# Synchronous_Rectification_and_Filtering.net
KiCad netlist of a schematic drawn in Altium Designer
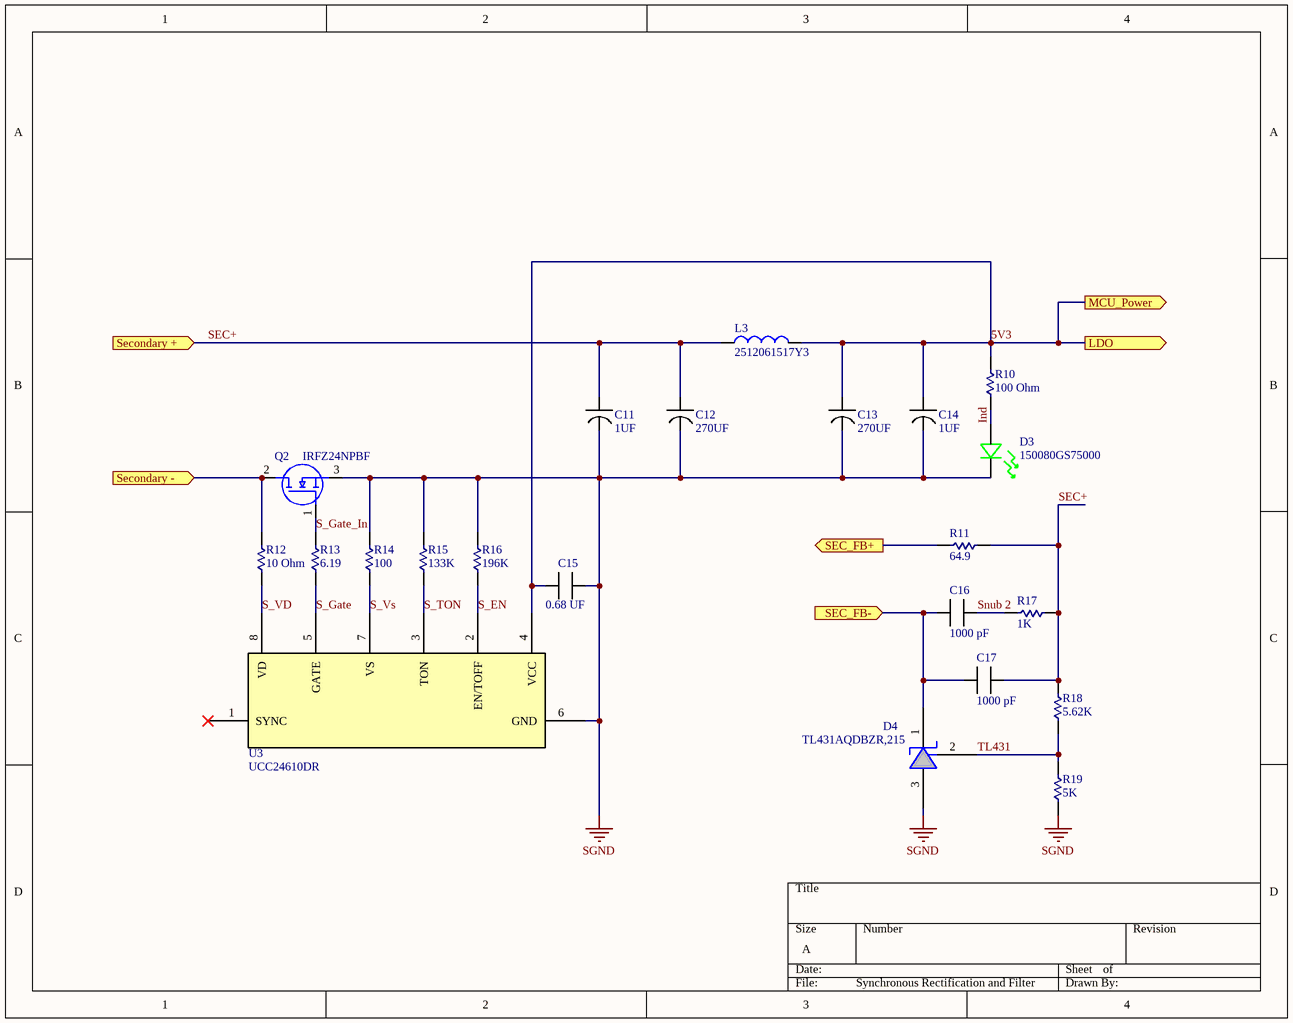
[diagram p0: Synchronous Rectification and Filtering.SchDoc]

(export (version "E")
  (design (tool "Eeschema 10.0.6"))
  (components
    (comp (ref "C11")
      (value "1UF")
      (footprint "CAP TANTALUM 1206")
      (description "Tantalum Capacitors - Solid SMD 10v 1uF 1206 10% ESR=10Ohms")
      (libsource (lib "SMPS Schlib") (part "T491A105K010AT"))
    )
    (comp (ref "C12")
      (value "270UF")
      (footprint "Alum Radial Cap 5mm")
      (description "Aluminum Electrolytic Capacitors - Radial Leaded 50V 270uF 105C 4k Hour Radial")
      (libsource (lib "SMPS Schlib") (part "ESY277M050AH4AA"))
    )
    (comp (ref "C13")
      (value "270UF")
      (footprint "Alum Radial Cap 5mm")
      (description "Aluminum Electrolytic Capacitors - Radial Leaded 50V 270uF 105C 4k Hour Radial")
      (libsource (lib "SMPS Schlib") (part "ESY277M050AH4AA"))
    )
    (comp (ref "C14")
      (value "1UF")
      (footprint "CAP TANTALUM 1206")
      (description "Tantalum Capacitors - Solid SMD 10v 1uF 1206 10% ESR=10Ohms")
      (libsource (lib "SMPS Schlib") (part "T491A105K010AT"))
    )
    (comp (ref "C15")
      (value "0.68 UF")
      (footprint "Res 0805")
      (description "Multilayer Ceramic Capacitors MLCC - SMD/SMT 50V 0.68uF X7R 0805 10% AEC-Q200")
      (libsource (lib "SMPS Schlib") (part "C0805C684K5RACAUTO7210"))
    )
    (comp (ref "C16")
      (value "1000 pF")
      (footprint "Cap 0603")
      (description "Multilayer Ceramic Capacitors MLCC - SMD/SMT 100V 1000pF X7R 0603 10%")
      (libsource (lib "SMPS Schlib") (part "C0603C102K1RAC7411"))
    )
    (comp (ref "C17")
      (value "1000 pF")
      (footprint "Cap 0603")
      (description "Multilayer Ceramic Capacitors MLCC - SMD/SMT 100V 1000pF X7R 0603 10%")
      (libsource (lib "SMPS Schlib") (part "C0603C102K1RAC7411"))
    )
    (comp (ref "D3")
      (value "150080GS75000")
      (footprint "Res 0805")
      (description "Standard LEDs - SMD WL-SMCW SMDMono TpVw Waterclr 0805 Green")
      (libsource (lib "SMPS Schlib") (part "150080GS75000"))
    )
    (comp (ref "D4")
      (value "TL431AQDBZR,215")
      (footprint "SOT23(TO-236AB)_NEX")
      (description "Shunt Voltage Reference IC Adjustable 2.495V 36 VV ±1% 100 mA TO-236AB")
      (libsource (lib "SMPS Schlib") (part "TL431AQDBZR,215"))
    )
    (comp (ref "L3")
      (value "2512061517Y3")
      (footprint "IND 1206")
      (description "Ferrite Beads MULTILAYER CHIP BEAD Z=150 OHM@100MHz 25")
      (libsource (lib "SMPS Schlib") (part "2512061517Y3"))
    )
    (comp (ref "Q2")
      (value "IRFZ24NPBF")
      (footprint "TO-220-3")
      (description "MOSFET MOSFT 55V 17A 70mOhm 13.3nC")
      (libsource (lib "SMPS Schlib") (part "IRFZ24NPBF"))
    )
    (comp (ref "R10")
      (value "100 Ohm")
      (footprint "Res 0805")
      (description "Thick Film Resistors - SMD 100 Ohms 125 mW 0805 1%")
      (libsource (lib "SMPS Schlib") (part "RC0805FR-07100RL"))
    )
    (comp (ref "R11")
      (value "64.9")
      (footprint "Res 0805")
      (description "Thin Film Resistors - SMD 1/8W 64.9 ohm 1% 50ppm")
      (libsource (lib "SMPS Schlib") (part "RT0805FRE0764R9L"))
    )
    (comp (ref "R12")
      (value "10 Ohm")
      (footprint "Res 0805")
      (description "Thick Film Resistors - SMD 10Ohms 1/8W 0805 5% 5% AEC-Q200")
      (libsource (lib "SMPS Schlib") (part "AR0805JR-0710RL"))
    )
    (comp (ref "R13")
      (value "6.19")
      (footprint "Res 0805")
      (description "Thick Film Resistors - SMD 6.19 Ohms 125 mW 0805 1%")
      (libsource (lib "SMPS Schlib") (part "RC0805FR-076R19L"))
    )
    (comp (ref "R14")
      (value "100")
      (footprint "Res 0805")
      (description "Thick Film Resistors - SMD 100 Ohms 125 mW 0805 1%")
      (libsource (lib "SMPS Schlib") (part "RC0805FR-07100RL"))
    )
    (comp (ref "R15")
      (value "133K")
      (footprint "Res 0805")
      (description "Thin Film Resistors - SMD 1/8W 133K ohm 1% 50ppm")
      (libsource (lib "SMPS Schlib") (part "RT0805FRE07133KL"))
    )
    (comp (ref "R16")
      (value "196K")
      (footprint "Res 0805")
      (description "Thin Film Resistors - SMD 1/8W 196K ohm 1% 50ppm")
      (libsource (lib "SMPS Schlib") (part "RT0805FRE07196KL"))
    )
    (comp (ref "R17")
      (value "1K")
      (footprint "Res 0805")
      (description "Thick Film Resistors - SMD 1 kOhms 250mW 0805 1 % AEC-Q200 Double Power Version")
      (libsource (lib "SMPS Schlib") (part "AC0805FR-7W1KL"))
    )
    (comp (ref "R18")
      (value "5.62K")
      (footprint "Res 0805")
      (description "Thin Film Resistors - SMD 1/8W 5.62K ohm .1% 25ppm")
      (libsource (lib "SMPS Schlib") (part "RT0805BRD075K62L"))
    )
    (comp (ref "R19")
      (value "5K")
      (footprint "Res 0805")
      (description "Thin Film Resistors - SMD 5K OHM .1% 25PPM 1/8W")
      (libsource (lib "SMPS Schlib") (part "CRT0805-BY-5001EAS"))
    )
    (comp (ref "U3")
      (value "UCC24610DR")
      (footprint "SOIC-8")
      (description "Gate Drivers Secondary Side Sync Rectifier Controller")
      (libsource (lib "SMPS Schlib") (part "UCC24610DR"))
    )
  )
  (nets
    (net (code "1") (name "/5V3") (class "Default")
      (node (ref "C13") (pin "1") (pinfunction "1_1") (pintype "passive"))
      (node (ref "C14") (pin "1") (pinfunction "1_1") (pintype "passive"))
      (node (ref "C15") (pin "2") (pinfunction "2_2") (pintype "passive"))
      (node (ref "L3") (pin "2") (pinfunction "2_2") (pintype "passive"))
      (node (ref "R10") (pin "2") (pinfunction "B_2") (pintype "passive"))
      (node (ref "U3") (pin "4") (pinfunction "VCC_4") (pintype "passive"))
    )
    (net (code "2") (name "/Ind") (class "Default")
      (node (ref "D3") (pin "2") (pinfunction "2_2") (pintype "passive"))
      (node (ref "R10") (pin "1") (pinfunction "A_1") (pintype "passive"))
    )
    (net (code "3") (name "/SEC+") (class "Default")
      (node (ref "C11") (pin "1") (pinfunction "1_1") (pintype "passive"))
      (node (ref "C12") (pin "1") (pinfunction "1_1") (pintype "passive"))
      (node (ref "C17") (pin "1") (pinfunction "1_1") (pintype "passive"))
      (node (ref "L3") (pin "1") (pinfunction "1_1") (pintype "passive"))
      (node (ref "R11") (pin "1") (pinfunction "A_1") (pintype "passive"))
      (node (ref "R17") (pin "1") (pinfunction "A_1") (pintype "passive"))
      (node (ref "R18") (pin "2") (pinfunction "B_2") (pintype "passive"))
    )
    (net (code "4") (name "/SEC_FB+") (class "Default")
      (node (ref "R11") (pin "2") (pinfunction "B_2") (pintype "passive"))
    )
    (net (code "5") (name "/SEC_FB-") (class "Default")
      (node (ref "C16") (pin "2") (pinfunction "2_2") (pintype "passive"))
      (node (ref "C17") (pin "2") (pinfunction "2_2") (pintype "passive"))
      (node (ref "D4") (pin "1") (pinfunction "1_1") (pintype "passive"))
    )
    (net (code "6") (name "/S_EN") (class "Default")
      (node (ref "R16") (pin "1") (pinfunction "A_1") (pintype "passive"))
      (node (ref "U3") (pin "2") (pinfunction "EN/TOFF_2") (pintype "passive"))
    )
    (net (code "7") (name "/S_Gate") (class "Default")
      (node (ref "R13") (pin "1") (pinfunction "A_1") (pintype "passive"))
      (node (ref "U3") (pin "5") (pinfunction "GATE_5") (pintype "passive"))
    )
    (net (code "8") (name "/S_Gate_In") (class "Default")
      (node (ref "Q2") (pin "1") (pinfunction "G_1") (pintype "passive"))
      (node (ref "R13") (pin "2") (pinfunction "B_2") (pintype "passive"))
    )
    (net (code "9") (name "/S_TON") (class "Default")
      (node (ref "R15") (pin "1") (pinfunction "A_1") (pintype "passive"))
      (node (ref "U3") (pin "3") (pinfunction "TON_3") (pintype "passive"))
    )
    (net (code "10") (name "/S_VD") (class "Default")
      (node (ref "R12") (pin "1") (pinfunction "A_1") (pintype "passive"))
      (node (ref "U3") (pin "8") (pinfunction "VD_8") (pintype "passive"))
    )
    (net (code "11") (name "/S_Vs") (class "Default")
      (node (ref "R14") (pin "1") (pinfunction "A_1") (pintype "passive"))
      (node (ref "U3") (pin "7") (pinfunction "VS_7") (pintype "passive"))
    )
    (net (code "12") (name "/Secondary -") (class "Default")
      (node (ref "Q2") (pin "2") (pinfunction "D_2") (pintype "passive"))
      (node (ref "R12") (pin "2") (pinfunction "B_2") (pintype "passive"))
    )
    (net (code "13") (name "/Snub 2") (class "Default")
      (node (ref "C16") (pin "1") (pinfunction "1_1") (pintype "passive"))
      (node (ref "R17") (pin "2") (pinfunction "B_2") (pintype "passive"))
    )
    (net (code "14") (name "/TL431") (class "Default")
      (node (ref "D4") (pin "2") (pinfunction "2_2") (pintype "passive"))
      (node (ref "R18") (pin "1") (pinfunction "A_1") (pintype "passive"))
      (node (ref "R19") (pin "2") (pinfunction "B_2") (pintype "passive"))
    )
    (net (code "15") (name "SGND") (class "Default")
      (node (ref "C11") (pin "2") (pinfunction "2_2") (pintype "passive"))
      (node (ref "C12") (pin "2") (pinfunction "2_2") (pintype "passive"))
      (node (ref "C13") (pin "2") (pinfunction "2_2") (pintype "passive"))
      (node (ref "C14") (pin "2") (pinfunction "2_2") (pintype "passive"))
      (node (ref "C15") (pin "1") (pinfunction "1_1") (pintype "passive"))
      (node (ref "D3") (pin "1") (pinfunction "1_1") (pintype "passive"))
      (node (ref "D4") (pin "3") (pinfunction "3_3") (pintype "passive"))
      (node (ref "Q2") (pin "3") (pinfunction "S_3") (pintype "passive"))
      (node (ref "R14") (pin "2") (pinfunction "B_2") (pintype "passive"))
      (node (ref "R15") (pin "2") (pinfunction "B_2") (pintype "passive"))
      (node (ref "R16") (pin "2") (pinfunction "B_2") (pintype "passive"))
      (node (ref "R19") (pin "1") (pinfunction "A_1") (pintype "passive"))
      (node (ref "U3") (pin "6") (pinfunction "GND_6") (pintype "passive"))
    )
    (net (code "16") (name "unconnected-(U3-SYNC-Pad1)") (class "Default")
      (node (ref "U3") (pin "1") (pinfunction "SYNC_1") (pintype "passive+no_connect"))
    )
  )
)
